# ElectronPhotonTestHarness.net
KiCad netlist of a schematic drawn in EAGLE
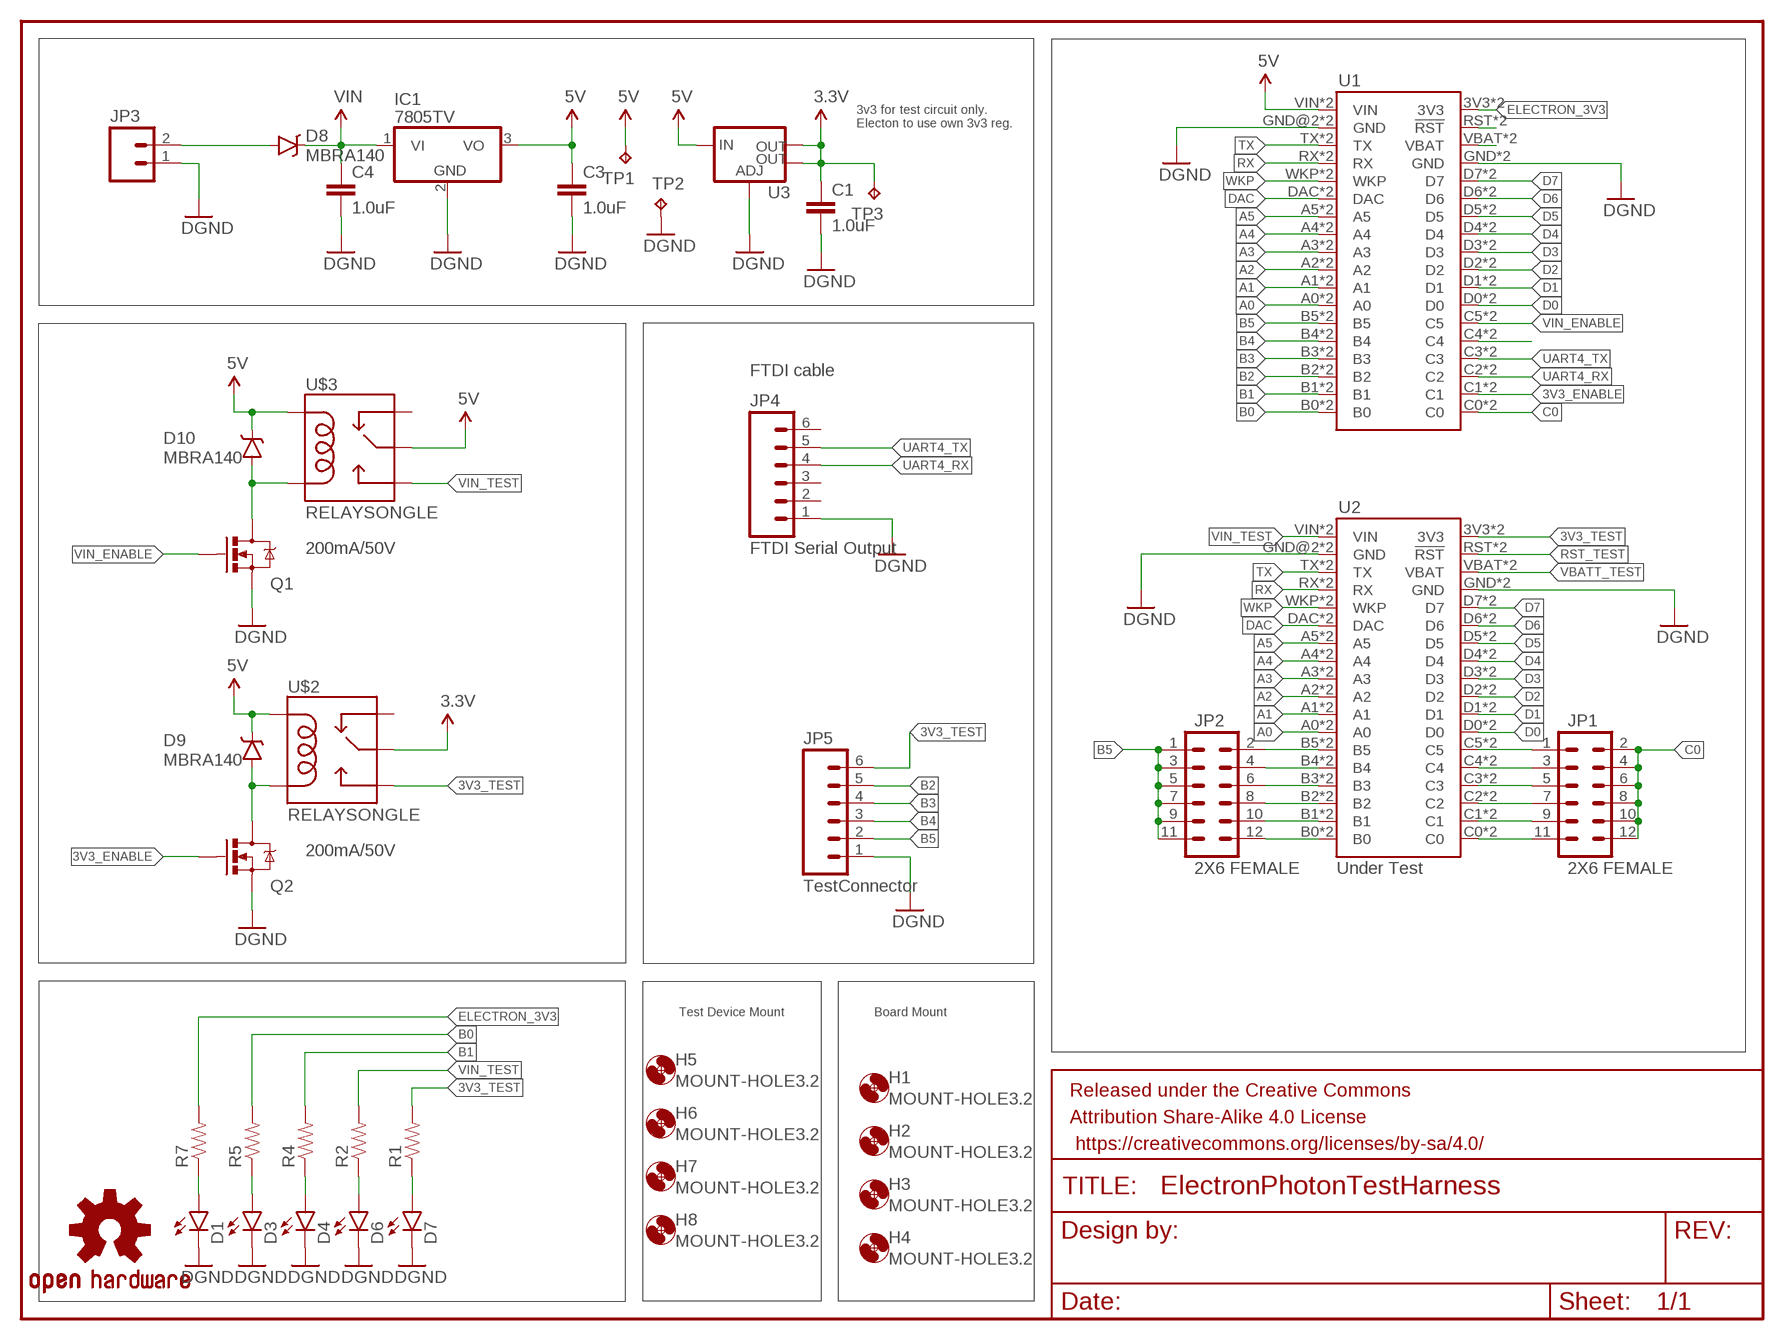
[diagram p0: schematic, sheet 1]

(export (version "E")
  (design (tool "Eeschema 10.0.6"))
  (components
    (comp (ref "C1")
      (value "1.0uF")
      (footprint "eagle-import:0805-CAP")
      (libsource (lib "eagle-import") (part "1.0UF-25V-+80/-20(0805){dblquote}"))
    )
    (comp (ref "C3")
      (value "1.0uF")
      (footprint "eagle-import:0805-CAP")
      (libsource (lib "eagle-import") (part "1.0UF-25V-+80/-20(0805){dblquote}"))
    )
    (comp (ref "C4")
      (value "1.0uF")
      (footprint "eagle-import:0805-CAP")
      (libsource (lib "eagle-import") (part "1.0UF-25V-+80/-20(0805){dblquote}"))
    )
    (comp (ref "D1")
      (value "LED1206-BOTTOM")
      (footprint "eagle-import:LED-1206-BOTTOM")
      (libsource (lib "eagle-import") (part "LED1206-BOTTOM"))
    )
    (comp (ref "D3")
      (value "LED1206")
      (footprint "eagle-import:LED-1206")
      (libsource (lib "eagle-import") (part "LED1206"))
    )
    (comp (ref "D4")
      (value "LED1206")
      (footprint "eagle-import:LED-1206")
      (libsource (lib "eagle-import") (part "LED1206"))
    )
    (comp (ref "D6")
      (value "LED1206")
      (footprint "eagle-import:LED-1206")
      (libsource (lib "eagle-import") (part "LED1206"))
    )
    (comp (ref "D7")
      (value "LED1206")
      (footprint "eagle-import:LED-1206")
      (libsource (lib "eagle-import") (part "LED1206"))
    )
    (comp (ref "D8")
      (value "MBRA140")
      (footprint "eagle-import:SMA-DIODE")
      (libsource (lib "eagle-import") (part "MBRA140"))
    )
    (comp (ref "D9")
      (value "MBRA140")
      (footprint "eagle-import:SMA-DIODE")
      (libsource (lib "eagle-import") (part "MBRA140"))
    )
    (comp (ref "D10")
      (value "MBRA140")
      (footprint "eagle-import:SMA-DIODE")
      (libsource (lib "eagle-import") (part "MBRA140"))
    )
    (comp (ref "FRAME1")
      (value "FRAME-LETTER")
      (footprint "eagle-import:CREATIVE_COMMONS")
      (libsource (lib "eagle-import") (part "FRAME-LETTER"))
    )
    (comp (ref "H1")
      (value "MOUNT-HOLE3.2")
      (footprint "eagle-import:3,2")
      (libsource (lib "eagle-import") (part "MOUNT-HOLE3.2"))
    )
    (comp (ref "H2")
      (value "MOUNT-HOLE3.2")
      (footprint "eagle-import:3,2")
      (libsource (lib "eagle-import") (part "MOUNT-HOLE3.2"))
    )
    (comp (ref "H3")
      (value "MOUNT-HOLE3.2")
      (footprint "eagle-import:3,2")
      (libsource (lib "eagle-import") (part "MOUNT-HOLE3.2"))
    )
    (comp (ref "H4")
      (value "MOUNT-HOLE3.2")
      (footprint "eagle-import:3,2")
      (libsource (lib "eagle-import") (part "MOUNT-HOLE3.2"))
    )
    (comp (ref "H5")
      (value "MOUNT-HOLE3.2")
      (footprint "eagle-import:3,2")
      (libsource (lib "eagle-import") (part "MOUNT-HOLE3.2"))
    )
    (comp (ref "H6")
      (value "MOUNT-HOLE3.2")
      (footprint "eagle-import:3,2")
      (libsource (lib "eagle-import") (part "MOUNT-HOLE3.2"))
    )
    (comp (ref "H7")
      (value "MOUNT-HOLE3.2")
      (footprint "eagle-import:3,2")
      (libsource (lib "eagle-import") (part "MOUNT-HOLE3.2"))
    )
    (comp (ref "H8")
      (value "MOUNT-HOLE3.2")
      (footprint "eagle-import:3,2")
      (libsource (lib "eagle-import") (part "MOUNT-HOLE3.2"))
    )
    (comp (ref "IC1")
      (value "7805TV")
      (footprint "eagle-import:TO220V")
      (libsource (lib "eagle-import") (part "78TV05"))
    )
    (comp (ref "JP1")
      (value "2X6 FEMALE")
      (footprint "eagle-import:2X6")
      (libsource (lib "eagle-import") (part "M06X2PTH_FEMALE"))
    )
    (comp (ref "JP2")
      (value "2X6 FEMALE")
      (footprint "eagle-import:2X6")
      (libsource (lib "eagle-import") (part "M06X2PTH_FEMALE"))
    )
    (comp (ref "JP3")
      (value "M025MM")
      (footprint "eagle-import:SCREWTERMINAL-5MM-2")
      (libsource (lib "eagle-import") (part "M025MM"))
    )
    (comp (ref "JP4")
      (value "FTDI Serial Output")
      (footprint "eagle-import:1X06")
      (libsource (lib "eagle-import") (part "M06SILK_FEMALE_PTH"))
    )
    (comp (ref "JP5")
      (value "TestConnector")
      (footprint "eagle-import:1X06")
      (libsource (lib "eagle-import") (part "M06SILK_FEMALE_PTH"))
    )
    (comp (ref "LOGO1")
      (value "OSHW-LOGOL")
      (footprint "eagle-import:OSHW-LOGO-L")
      (libsource (lib "eagle-import") (part "OSHW-LOGOL"))
    )
    (comp (ref "Q1")
      (value "200mA/50V")
      (footprint "eagle-import:SOT23-3")
      (libsource (lib "eagle-import") (part "MOSFET-NCHANNELBSS138"))
    )
    (comp (ref "Q2")
      (value "200mA/50V")
      (footprint "eagle-import:SOT23-3")
      (libsource (lib "eagle-import") (part "MOSFET-NCHANNELBSS138"))
    )
    (comp (ref "R1")
      (value "RESISTOR1206")
      (footprint "eagle-import:1206")
      (libsource (lib "eagle-import") (part "RESISTOR1206"))
    )
    (comp (ref "R2")
      (value "RESISTOR1206")
      (footprint "eagle-import:1206")
      (libsource (lib "eagle-import") (part "RESISTOR1206"))
    )
    (comp (ref "R4")
      (value "RESISTOR1206")
      (footprint "eagle-import:1206")
      (libsource (lib "eagle-import") (part "RESISTOR1206"))
    )
    (comp (ref "R5")
      (value "RESISTOR1206")
      (footprint "eagle-import:1206")
      (libsource (lib "eagle-import") (part "RESISTOR1206"))
    )
    (comp (ref "R7")
      (value "RESISTOR1206")
      (footprint "eagle-import:1206")
      (libsource (lib "eagle-import") (part "RESISTOR1206"))
    )
    (comp (ref "TP1")
      (value "TPTP12SQ")
      (footprint "eagle-import:TP12SQ")
      (libsource (lib "eagle-import") (part "TPTP12SQ"))
    )
    (comp (ref "TP2")
      (value "TPTP12SQ")
      (footprint "eagle-import:TP12SQ")
      (libsource (lib "eagle-import") (part "TPTP12SQ"))
    )
    (comp (ref "TP3")
      (value "TPTP12SQ")
      (footprint "eagle-import:TP12SQ")
      (libsource (lib "eagle-import") (part "TPTP12SQ"))
    )
    (comp (ref "U$2")
      (value "RELAYSONGLE")
      (footprint "eagle-import:SRD-5VDC-SL-C")
      (libsource (lib "eagle-import") (part "RELAYSONGLE"))
    )
    (comp (ref "U$3")
      (value "RELAYSONGLE")
      (footprint "eagle-import:SRD-5VDC-SL-C")
      (libsource (lib "eagle-import") (part "RELAYSONGLE"))
    )
    (comp (ref "U1")
      (value "ELECTRONDUALNAMED")
      (footprint "eagle-import:ELECTRON_SIMPLE_SILK_NAMES_DUAL")
      (libsource (lib "eagle-import") (part "ELECTRONDUALNAMED"))
    )
    (comp (ref "U2")
      (value "UnderTest")
      (footprint "eagle-import:ELECTRON_SIMPLE_SILK_NAMES_DUAL")
      (libsource (lib "eagle-import") (part "ELECTRONDUALNAMED"))
    )
    (comp (ref "U3")
      (value "V_REG_LM1117SOT223")
      (footprint "eagle-import:SOT223")
      (libsource (lib "eagle-import") (part "V_REG_LM1117SOT223"))
    )
  )
  (nets
    (net (code "1") (name "3.3V") (class "Default")
      (node (ref "C1") (pin "1") (pinfunction "1_1") (pintype "passive"))
      (node (ref "TP3") (pin "TP") (pinfunction "TP_TP") (pintype "input"))
      (node (ref "U$2") (pin "COMMON") (pinfunction "MAIN_COMMON") (pintype "bidirectional"))
      (node (ref "U3") (pin "2") (pinfunction "OUT_2") (pintype "output"))
      (node (ref "U3") (pin "4") (pinfunction "OUT_4") (pintype "output"))
    )
    (net (code "2") (name "3V3_ENABLE") (class "Default")
      (node (ref "Q2") (pin "1") (pinfunction "G_1") (pintype "passive"))
      (node (ref "U1") (pin "C1") (pinfunction "C1_C1") (pintype "bidirectional"))
      (node (ref "U1") (pin "C1_1") (pinfunction "C1_C1_1") (pintype "bidirectional"))
    )
    (net (code "3") (name "3V3_TEST") (class "Default")
      (node (ref "JP5") (pin "6") (pinfunction "6_6") (pintype "passive"))
      (node (ref "R1") (pin "2") (pinfunction "2_2") (pintype "passive"))
      (node (ref "U$2") (pin "OPEN") (pinfunction "NO_OPEN") (pintype "bidirectional"))
      (node (ref "U2") (pin "3V3") (pinfunction "3V3_3V3") (pintype "power_in"))
      (node (ref "U2") (pin "3V3_1") (pinfunction "3V3_3V3_1") (pintype "power_in"))
    )
    (net (code "4") (name "5V") (class "Default")
      (node (ref "C3") (pin "1") (pinfunction "1_1") (pintype "passive"))
      (node (ref "D10") (pin "C") (pinfunction "C_C") (pintype "passive"))
      (node (ref "D9") (pin "C") (pinfunction "C_C") (pintype "passive"))
      (node (ref "IC1") (pin "3") (pinfunction "VO_3") (pintype "passive"))
      (node (ref "TP1") (pin "TP") (pinfunction "TP_TP") (pintype "input"))
      (node (ref "U$2") (pin "COIL1") (pinfunction "COIL1_COIL1") (pintype "bidirectional"))
      (node (ref "U$3") (pin "COIL1") (pinfunction "COIL1_COIL1") (pintype "bidirectional"))
      (node (ref "U$3") (pin "COMMON") (pinfunction "MAIN_COMMON") (pintype "bidirectional"))
      (node (ref "U1") (pin "VIN") (pinfunction "VIN_VIN") (pintype "power_in"))
      (node (ref "U1") (pin "VIN_1B") (pinfunction "VIN_VIN_1B") (pintype "power_in"))
      (node (ref "U3") (pin "3") (pinfunction "IN_3") (pintype "input"))
    )
    (net (code "5") (name "A0") (class "Default")
      (node (ref "U1") (pin "A0") (pinfunction "A0_A0") (pintype "bidirectional"))
      (node (ref "U1") (pin "A0_1") (pinfunction "A0_A0_1") (pintype "bidirectional"))
      (node (ref "U2") (pin "A0") (pinfunction "A0_A0") (pintype "bidirectional"))
      (node (ref "U2") (pin "A0_1") (pinfunction "A0_A0_1") (pintype "bidirectional"))
    )
    (net (code "6") (name "A1") (class "Default")
      (node (ref "U1") (pin "A1") (pinfunction "A1_A1") (pintype "bidirectional"))
      (node (ref "U1") (pin "A1_1") (pinfunction "A1_A1_1") (pintype "bidirectional"))
      (node (ref "U2") (pin "A1") (pinfunction "A1_A1") (pintype "bidirectional"))
      (node (ref "U2") (pin "A1_1") (pinfunction "A1_A1_1") (pintype "bidirectional"))
    )
    (net (code "7") (name "A2") (class "Default")
      (node (ref "U1") (pin "A2") (pinfunction "A2_A2") (pintype "bidirectional"))
      (node (ref "U1") (pin "A2_1") (pinfunction "A2_A2_1") (pintype "bidirectional"))
      (node (ref "U2") (pin "A2") (pinfunction "A2_A2") (pintype "bidirectional"))
      (node (ref "U2") (pin "A2_1") (pinfunction "A2_A2_1") (pintype "bidirectional"))
    )
    (net (code "8") (name "A3") (class "Default")
      (node (ref "U1") (pin "A3") (pinfunction "A3_A3") (pintype "bidirectional"))
      (node (ref "U1") (pin "A3_1") (pinfunction "A3_A3_1") (pintype "bidirectional"))
      (node (ref "U2") (pin "A3") (pinfunction "A3_A3") (pintype "bidirectional"))
      (node (ref "U2") (pin "A3_1") (pinfunction "A3_A3_1") (pintype "bidirectional"))
    )
    (net (code "9") (name "A4") (class "Default")
      (node (ref "U1") (pin "A4") (pinfunction "A4_A4") (pintype "bidirectional"))
      (node (ref "U1") (pin "A4_1") (pinfunction "A4_A4_1") (pintype "bidirectional"))
      (node (ref "U2") (pin "A4") (pinfunction "A4_A4") (pintype "bidirectional"))
      (node (ref "U2") (pin "A4_1") (pinfunction "A4_A4_1") (pintype "bidirectional"))
    )
    (net (code "10") (name "A5") (class "Default")
      (node (ref "U1") (pin "A5") (pinfunction "A5_A5") (pintype "bidirectional"))
      (node (ref "U1") (pin "A5_1") (pinfunction "A5_A5_1") (pintype "bidirectional"))
      (node (ref "U2") (pin "A5") (pinfunction "A5_A5") (pintype "bidirectional"))
      (node (ref "U2") (pin "A5_1") (pinfunction "A5_A5_1") (pintype "bidirectional"))
    )
    (net (code "11") (name "B0") (class "Default")
      (node (ref "R5") (pin "2") (pinfunction "2_2") (pintype "passive"))
      (node (ref "U1") (pin "B0") (pinfunction "B0_B0") (pintype "bidirectional"))
      (node (ref "U1") (pin "B0_1") (pinfunction "B0_B0_1") (pintype "bidirectional"))
    )
    (net (code "12") (name "B1") (class "Default")
      (node (ref "R4") (pin "2") (pinfunction "2_2") (pintype "passive"))
      (node (ref "U1") (pin "B1") (pinfunction "B1_B1") (pintype "bidirectional"))
      (node (ref "U1") (pin "B1_1") (pinfunction "B1_B1_1") (pintype "bidirectional"))
    )
    (net (code "13") (name "B2") (class "Default")
      (node (ref "JP5") (pin "5") (pinfunction "5_5") (pintype "passive"))
      (node (ref "U1") (pin "B2") (pinfunction "B2_B2") (pintype "bidirectional"))
      (node (ref "U1") (pin "B2_1") (pinfunction "B2_B2_1") (pintype "bidirectional"))
    )
    (net (code "14") (name "B3") (class "Default")
      (node (ref "JP5") (pin "4") (pinfunction "4_4") (pintype "passive"))
      (node (ref "U1") (pin "B3") (pinfunction "B3_B3") (pintype "bidirectional"))
      (node (ref "U1") (pin "B3_1") (pinfunction "B3_B3_1") (pintype "bidirectional"))
    )
    (net (code "15") (name "B4") (class "Default")
      (node (ref "JP5") (pin "3") (pinfunction "3_3") (pintype "passive"))
      (node (ref "U1") (pin "B4") (pinfunction "B4_B4") (pintype "bidirectional"))
      (node (ref "U1") (pin "B4_1") (pinfunction "B4_B4_1") (pintype "bidirectional"))
    )
    (net (code "16") (name "B5") (class "Default")
      (node (ref "JP2") (pin "1") (pinfunction "1_1") (pintype "passive"))
      (node (ref "JP2") (pin "11") (pinfunction "11_11") (pintype "passive"))
      (node (ref "JP2") (pin "3") (pinfunction "3_3") (pintype "passive"))
      (node (ref "JP2") (pin "5") (pinfunction "5_5") (pintype "passive"))
      (node (ref "JP2") (pin "7") (pinfunction "7_7") (pintype "passive"))
      (node (ref "JP2") (pin "9") (pinfunction "9_9") (pintype "passive"))
      (node (ref "JP5") (pin "2") (pinfunction "2_2") (pintype "passive"))
      (node (ref "U1") (pin "B5") (pinfunction "B5_B5") (pintype "bidirectional"))
      (node (ref "U1") (pin "B5_1") (pinfunction "B5_B5_1") (pintype "bidirectional"))
    )
    (net (code "17") (name "C0") (class "Default")
      (node (ref "JP1") (pin "10") (pinfunction "10_10") (pintype "passive"))
      (node (ref "JP1") (pin "12") (pinfunction "12_12") (pintype "passive"))
      (node (ref "JP1") (pin "2") (pinfunction "2_2") (pintype "passive"))
      (node (ref "JP1") (pin "4") (pinfunction "4_4") (pintype "passive"))
      (node (ref "JP1") (pin "6") (pinfunction "6_6") (pintype "passive"))
      (node (ref "JP1") (pin "8") (pinfunction "8_8") (pintype "passive"))
      (node (ref "U1") (pin "C0") (pinfunction "C0_C0") (pintype "bidirectional"))
      (node (ref "U1") (pin "C0_1") (pinfunction "C0_C0_1") (pintype "bidirectional"))
    )
    (net (code "18") (name "D0") (class "Default")
      (node (ref "U1") (pin "D0") (pinfunction "D0_D0") (pintype "bidirectional"))
      (node (ref "U1") (pin "D0_1") (pinfunction "D0_D0_1") (pintype "bidirectional"))
      (node (ref "U2") (pin "D0") (pinfunction "D0_D0") (pintype "bidirectional"))
      (node (ref "U2") (pin "D0_1") (pinfunction "D0_D0_1") (pintype "bidirectional"))
    )
    (net (code "19") (name "D1") (class "Default")
      (node (ref "U1") (pin "D1") (pinfunction "D1_D1") (pintype "bidirectional"))
      (node (ref "U1") (pin "D1_1") (pinfunction "D1_D1_1") (pintype "bidirectional"))
      (node (ref "U2") (pin "D1") (pinfunction "D1_D1") (pintype "bidirectional"))
      (node (ref "U2") (pin "D1_1") (pinfunction "D1_D1_1") (pintype "bidirectional"))
    )
    (net (code "20") (name "D2") (class "Default")
      (node (ref "U1") (pin "D2") (pinfunction "D2_D2") (pintype "bidirectional"))
      (node (ref "U1") (pin "D2_1") (pinfunction "D2_D2_1") (pintype "bidirectional"))
      (node (ref "U2") (pin "D2") (pinfunction "D2_D2") (pintype "bidirectional"))
      (node (ref "U2") (pin "D2_1") (pinfunction "D2_D2_1") (pintype "bidirectional"))
    )
    (net (code "21") (name "D3") (class "Default")
      (node (ref "U1") (pin "D3") (pinfunction "D3_D3") (pintype "bidirectional"))
      (node (ref "U1") (pin "D3_1") (pinfunction "D3_D3_1") (pintype "bidirectional"))
      (node (ref "U2") (pin "D3") (pinfunction "D3_D3") (pintype "bidirectional"))
      (node (ref "U2") (pin "D3_1") (pinfunction "D3_D3_1") (pintype "bidirectional"))
    )
    (net (code "22") (name "D4") (class "Default")
      (node (ref "U1") (pin "D4") (pinfunction "D4_D4") (pintype "bidirectional"))
      (node (ref "U1") (pin "D4_1") (pinfunction "D4_D4_1") (pintype "bidirectional"))
      (node (ref "U2") (pin "D4") (pinfunction "D4_D4") (pintype "bidirectional"))
      (node (ref "U2") (pin "D4_1") (pinfunction "D4_D4_1") (pintype "bidirectional"))
    )
    (net (code "23") (name "D5") (class "Default")
      (node (ref "U1") (pin "D5") (pinfunction "D5_D5") (pintype "bidirectional"))
      (node (ref "U1") (pin "D5_1") (pinfunction "D5_D5_1") (pintype "bidirectional"))
      (node (ref "U2") (pin "D5") (pinfunction "D5_D5") (pintype "bidirectional"))
      (node (ref "U2") (pin "D5_1") (pinfunction "D5_D5_1") (pintype "bidirectional"))
    )
    (net (code "24") (name "D6") (class "Default")
      (node (ref "U1") (pin "D6") (pinfunction "D6_D6") (pintype "bidirectional"))
      (node (ref "U1") (pin "D6_1") (pinfunction "D6_D6_1") (pintype "bidirectional"))
      (node (ref "U2") (pin "D6") (pinfunction "D6_D6") (pintype "bidirectional"))
      (node (ref "U2") (pin "D6_1") (pinfunction "D6_D6_1") (pintype "bidirectional"))
    )
    (net (code "25") (name "D7") (class "Default")
      (node (ref "U1") (pin "D7") (pinfunction "D7_D7") (pintype "bidirectional"))
      (node (ref "U1") (pin "D7_1") (pinfunction "D7_D7_1") (pintype "bidirectional"))
      (node (ref "U2") (pin "D7") (pinfunction "D7_D7") (pintype "bidirectional"))
      (node (ref "U2") (pin "D7_1") (pinfunction "D7_D7_1") (pintype "bidirectional"))
    )
    (net (code "26") (name "DAC") (class "Default")
      (node (ref "U1") (pin "DAC") (pinfunction "DAC_DAC") (pintype "bidirectional"))
      (node (ref "U1") (pin "DAC_1") (pinfunction "DAC_DAC_1") (pintype "bidirectional"))
      (node (ref "U2") (pin "DAC") (pinfunction "DAC_DAC") (pintype "bidirectional"))
      (node (ref "U2") (pin "DAC_1") (pinfunction "DAC_DAC_1") (pintype "bidirectional"))
    )
    (net (code "27") (name "DGND") (class "Default")
      (node (ref "C1") (pin "2") (pinfunction "2_2") (pintype "passive"))
      (node (ref "C3") (pin "2") (pinfunction "2_2") (pintype "passive"))
      (node (ref "C4") (pin "2") (pinfunction "2_2") (pintype "passive"))
      (node (ref "D1") (pin "C") (pinfunction "C_C") (pintype "passive"))
      (node (ref "D3") (pin "C") (pinfunction "C_C") (pintype "passive"))
      (node (ref "D4") (pin "C") (pinfunction "C_C") (pintype "passive"))
      (node (ref "D6") (pin "C") (pinfunction "C_C") (pintype "passive"))
      (node (ref "D7") (pin "C") (pinfunction "C_C") (pintype "passive"))
      (node (ref "IC1") (pin "2") (pinfunction "GND_2") (pintype "passive"))
      (node (ref "JP3") (pin "1") (pinfunction "1_1") (pintype "passive"))
      (node (ref "JP4") (pin "1") (pinfunction "1_1") (pintype "passive"))
      (node (ref "JP5") (pin "1") (pinfunction "1_1") (pintype "passive"))
      (node (ref "Q1") (pin "2") (pinfunction "S_2") (pintype "passive"))
      (node (ref "Q2") (pin "2") (pinfunction "S_2") (pintype "passive"))
      (node (ref "TP2") (pin "TP") (pinfunction "TP_TP") (pintype "input"))
      (node (ref "U1") (pin "GND") (pinfunction "GND_GND") (pintype "power_in"))
      (node (ref "U1") (pin "GND@2") (pinfunction "GND_GND@2") (pintype "power_in"))
      (node (ref "U1") (pin "GND_1") (pinfunction "GND_GND_1") (pintype "power_in"))
      (node (ref "U1") (pin "GND_1B") (pinfunction "GND_GND_1B") (pintype "power_in"))
      (node (ref "U2") (pin "GND") (pinfunction "GND_GND") (pintype "power_in"))
      (node (ref "U2") (pin "GND@2") (pinfunction "GND_GND@2") (pintype "power_in"))
      (node (ref "U2") (pin "GND_1") (pinfunction "GND_GND_1") (pintype "power_in"))
      (node (ref "U2") (pin "GND_1B") (pinfunction "GND_GND_1B") (pintype "power_in"))
      (node (ref "U3") (pin "1") (pinfunction "ADJ_1") (pintype "input"))
    )
    (net (code "28") (name "ELECTRON_3V3") (class "Default")
      (node (ref "R7") (pin "2") (pinfunction "2_2") (pintype "passive"))
      (node (ref "U1") (pin "3V3") (pinfunction "3V3_3V3") (pintype "power_in"))
      (node (ref "U1") (pin "3V3_1") (pinfunction "3V3_3V3_1") (pintype "power_in"))
    )
    (net (code "29") (name "Net-(D1-PadA)") (class "Default")
      (node (ref "D1") (pin "A") (pinfunction "A_A") (pintype "passive"))
      (node (ref "R7") (pin "1") (pinfunction "1_1") (pintype "passive"))
    )
    (net (code "30") (name "Net-(D3-PadA)") (class "Default")
      (node (ref "D3") (pin "A") (pinfunction "A_A") (pintype "passive"))
      (node (ref "R5") (pin "1") (pinfunction "1_1") (pintype "passive"))
    )
    (net (code "31") (name "Net-(D4-PadA)") (class "Default")
      (node (ref "D4") (pin "A") (pinfunction "A_A") (pintype "passive"))
      (node (ref "R4") (pin "1") (pinfunction "1_1") (pintype "passive"))
    )
    (net (code "32") (name "Net-(D6-PadA)") (class "Default")
      (node (ref "D6") (pin "A") (pinfunction "A_A") (pintype "passive"))
      (node (ref "R2") (pin "1") (pinfunction "1_1") (pintype "passive"))
    )
    (net (code "33") (name "Net-(D7-PadA)") (class "Default")
      (node (ref "D7") (pin "A") (pinfunction "A_A") (pintype "passive"))
      (node (ref "R1") (pin "1") (pinfunction "1_1") (pintype "passive"))
    )
    (net (code "34") (name "Net-(D8-PadA)") (class "Default")
      (node (ref "D8") (pin "A") (pinfunction "A_A") (pintype "passive"))
      (node (ref "JP3") (pin "2") (pinfunction "2_2") (pintype "passive"))
    )
    (net (code "35") (name "Net-(JP1-Pad1)") (class "Default")
      (node (ref "JP1") (pin "1") (pinfunction "1_1") (pintype "passive"))
      (node (ref "U2") (pin "C5") (pinfunction "C5_C5") (pintype "bidirectional"))
      (node (ref "U2") (pin "C5_1") (pinfunction "C5_C5_1") (pintype "bidirectional"))
    )
    (net (code "36") (name "Net-(JP1-Pad3)") (class "Default")
      (node (ref "JP1") (pin "3") (pinfunction "3_3") (pintype "passive"))
      (node (ref "U2") (pin "C4") (pinfunction "C4_C4") (pintype "bidirectional"))
      (node (ref "U2") (pin "C4_1") (pinfunction "C4_C4_1") (pintype "bidirectional"))
    )
    (net (code "37") (name "Net-(JP1-Pad5)") (class "Default")
      (node (ref "JP1") (pin "5") (pinfunction "5_5") (pintype "passive"))
      (node (ref "U2") (pin "C3") (pinfunction "C3_C3") (pintype "bidirectional"))
      (node (ref "U2") (pin "C3_1") (pinfunction "C3_C3_1") (pintype "bidirectional"))
    )
    (net (code "38") (name "Net-(JP1-Pad7)") (class "Default")
      (node (ref "JP1") (pin "7") (pinfunction "7_7") (pintype "passive"))
      (node (ref "U2") (pin "C2") (pinfunction "C2_C2") (pintype "bidirectional"))
      (node (ref "U2") (pin "C2_1") (pinfunction "C2_C2_1") (pintype "bidirectional"))
    )
    (net (code "39") (name "Net-(JP1-Pad9)") (class "Default")
      (node (ref "JP1") (pin "9") (pinfunction "9_9") (pintype "passive"))
      (node (ref "U2") (pin "C1") (pinfunction "C1_C1") (pintype "bidirectional"))
      (node (ref "U2") (pin "C1_1") (pinfunction "C1_C1_1") (pintype "bidirectional"))
    )
    (net (code "40") (name "Net-(JP1-Pad11)") (class "Default")
      (node (ref "JP1") (pin "11") (pinfunction "11_11") (pintype "passive"))
      (node (ref "U2") (pin "C0") (pinfunction "C0_C0") (pintype "bidirectional"))
      (node (ref "U2") (pin "C0_1") (pinfunction "C0_C0_1") (pintype "bidirectional"))
    )
    (net (code "41") (name "Net-(JP2-Pad2)") (class "Default")
      (node (ref "JP2") (pin "2") (pinfunction "2_2") (pintype "passive"))
      (node (ref "U2") (pin "B5") (pinfunction "B5_B5") (pintype "bidirectional"))
      (node (ref "U2") (pin "B5_1") (pinfunction "B5_B5_1") (pintype "bidirectional"))
    )
    (net (code "42") (name "Net-(JP2-Pad4)") (class "Default")
      (node (ref "JP2") (pin "4") (pinfunction "4_4") (pintype "passive"))
      (node (ref "U2") (pin "B4") (pinfunction "B4_B4") (pintype "bidirectional"))
      (node (ref "U2") (pin "B4_1") (pinfunction "B4_B4_1") (pintype "bidirectional"))
    )
    (net (code "43") (name "Net-(JP2-Pad6)") (class "Default")
      (node (ref "JP2") (pin "6") (pinfunction "6_6") (pintype "passive"))
      (node (ref "U2") (pin "B3") (pinfunction "B3_B3") (pintype "bidirectional"))
      (node (ref "U2") (pin "B3_1") (pinfunction "B3_B3_1") (pintype "bidirectional"))
    )
    (net (code "44") (name "Net-(JP2-Pad8)") (class "Default")
      (node (ref "JP2") (pin "8") (pinfunction "8_8") (pintype "passive"))
      (node (ref "U2") (pin "B2") (pinfunction "B2_B2") (pintype "bidirectional"))
      (node (ref "U2") (pin "B2_1") (pinfunction "B2_B2_1") (pintype "bidirectional"))
    )
    (net (code "45") (name "Net-(JP2-Pad10)") (class "Default")
      (node (ref "JP2") (pin "10") (pinfunction "10_10") (pintype "passive"))
      (node (ref "U2") (pin "B1") (pinfunction "B1_B1") (pintype "bidirectional"))
      (node (ref "U2") (pin "B1_1") (pinfunction "B1_B1_1") (pintype "bidirectional"))
    )
    (net (code "46") (name "Net-(JP2-Pad12)") (class "Default")
      (node (ref "JP2") (pin "12") (pinfunction "12_12") (pintype "passive"))
      (node (ref "U2") (pin "B0") (pinfunction "B0_B0") (pintype "bidirectional"))
      (node (ref "U2") (pin "B0_1") (pinfunction "B0_B0_1") (pintype "bidirectional"))
    )
    (net (code "47") (name "Net-(Q1-D)") (class "Default")
      (node (ref "D10") (pin "A") (pinfunction "A_A") (pintype "passive"))
      (node (ref "Q1") (pin "3") (pinfunction "D_3") (pintype "passive"))
      (node (ref "U$3") (pin "COIL2") (pinfunction "COIL2_COIL2") (pintype "bidirectional"))
    )
    (net (code "48") (name "Net-(Q2-D)") (class "Default")
      (node (ref "D9") (pin "A") (pinfunction "A_A") (pintype "passive"))
      (node (ref "Q2") (pin "3") (pinfunction "D_3") (pintype "passive"))
      (node (ref "U$2") (pin "COIL2") (pinfunction "COIL2_COIL2") (pintype "bidirectional"))
    )
    (net (code "49") (name "Net-(U1-C4-PadC4_1)") (class "Default")
      (node (ref "U1") (pin "C4") (pinfunction "C4_C4") (pintype "bidirectional"))
      (node (ref "U1") (pin "C4_1") (pinfunction "C4_C4_1") (pintype "bidirectional"))
    )
    (net (code "50") (name "Net-(U1-PadVBAT)") (class "Default")
      (node (ref "U1") (pin "VBAT") (pinfunction "VBAT_VBAT") (pintype "passive"))
      (node (ref "U1") (pin "VBATT_1") (pinfunction "VBAT_VBATT_1") (pintype "passive"))
    )
    (net (code "51") (name "Net-(U1-~{RST}-PadRST)") (class "Default")
      (node (ref "U1") (pin "RST") (pinfunction "~{RST}_RST") (pintype "bidirectional"))
      (node (ref "U1") (pin "RST_1") (pinfunction "~{RST}_RST_1") (pintype "bidirectional"))
    )
    (net (code "52") (name "RST_TEST") (class "Default")
      (node (ref "U2") (pin "RST") (pinfunction "~{RST}_RST") (pintype "bidirectional"))
      (node (ref "U2") (pin "RST_1") (pinfunction "~{RST}_RST_1") (pintype "bidirectional"))
    )
    (net (code "53") (name "RX") (class "Default")
      (node (ref "U1") (pin "RX") (pinfunction "RX_RX") (pintype "bidirectional"))
      (node (ref "U1") (pin "RX_1") (pinfunction "RX_RX_1") (pintype "bidirectional"))
      (node (ref "U2") (pin "RX") (pinfunction "RX_RX") (pintype "bidirectional"))
      (node (ref "U2") (pin "RX_1") (pinfunction "RX_RX_1") (pintype "bidirectional"))
    )
    (net (code "54") (name "TX") (class "Default")
      (node (ref "U1") (pin "TX") (pinfunction "TX_TX") (pintype "bidirectional"))
      (node (ref "U1") (pin "TX_1") (pinfunction "TX_TX_1") (pintype "bidirectional"))
      (node (ref "U2") (pin "TX") (pinfunction "TX_TX") (pintype "bidirectional"))
      (node (ref "U2") (pin "TX_1") (pinfunction "TX_TX_1") (pintype "bidirectional"))
    )
    (net (code "55") (name "UART4_RX") (class "Default")
      (node (ref "JP4") (pin "4") (pinfunction "4_4") (pintype "passive"))
      (node (ref "U1") (pin "C2") (pinfunction "C2_C2") (pintype "bidirectional"))
      (node (ref "U1") (pin "C2_1") (pinfunction "C2_C2_1") (pintype "bidirectional"))
    )
    (net (code "56") (name "UART4_TX") (class "Default")
      (node (ref "JP4") (pin "5") (pinfunction "5_5") (pintype "passive"))
      (node (ref "U1") (pin "C3") (pinfunction "C3_C3") (pintype "bidirectional"))
      (node (ref "U1") (pin "C3_1") (pinfunction "C3_C3_1") (pintype "bidirectional"))
    )
    (net (code "57") (name "VBATT_TEST") (class "Default")
      (node (ref "U2") (pin "VBAT") (pinfunction "VBAT_VBAT") (pintype "passive"))
      (node (ref "U2") (pin "VBATT_1") (pinfunction "VBAT_VBATT_1") (pintype "passive"))
    )
    (net (code "58") (name "VIN") (class "Default")
      (node (ref "C4") (pin "1") (pinfunction "1_1") (pintype "passive"))
      (node (ref "D8") (pin "C") (pinfunction "C_C") (pintype "passive"))
      (node (ref "IC1") (pin "1") (pinfunction "VI_1") (pintype "input"))
    )
    (net (code "59") (name "VIN_ENABLE") (class "Default")
      (node (ref "Q1") (pin "1") (pinfunction "G_1") (pintype "passive"))
      (node (ref "U1") (pin "C5") (pinfunction "C5_C5") (pintype "bidirectional"))
      (node (ref "U1") (pin "C5_1") (pinfunction "C5_C5_1") (pintype "bidirectional"))
    )
    (net (code "60") (name "VIN_TEST") (class "Default")
      (node (ref "R2") (pin "2") (pinfunction "2_2") (pintype "passive"))
      (node (ref "U$3") (pin "OPEN") (pinfunction "NO_OPEN") (pintype "bidirectional"))
      (node (ref "U2") (pin "VIN") (pinfunction "VIN_VIN") (pintype "power_in"))
      (node (ref "U2") (pin "VIN_1B") (pinfunction "VIN_VIN_1B") (pintype "power_in"))
    )
    (net (code "61") (name "WKP") (class "Default")
      (node (ref "U1") (pin "WKP") (pinfunction "WKP_WKP") (pintype "bidirectional"))
      (node (ref "U1") (pin "WKP_1") (pinfunction "WKP_WKP_1") (pintype "bidirectional"))
      (node (ref "U2") (pin "WKP") (pinfunction "WKP_WKP") (pintype "bidirectional"))
      (node (ref "U2") (pin "WKP_1") (pinfunction "WKP_WKP_1") (pintype "bidirectional"))
    )
    (net (code "62") (name "unconnected-(JP4-Pad2)") (class "Default")
      (node (ref "JP4") (pin "2") (pinfunction "2_2") (pintype "passive"))
    )
    (net (code "63") (name "unconnected-(JP4-Pad3)") (class "Default")
      (node (ref "JP4") (pin "3") (pinfunction "3_3") (pintype "passive"))
    )
    (net (code "64") (name "unconnected-(JP4-Pad6)") (class "Default")
      (node (ref "JP4") (pin "6") (pinfunction "6_6") (pintype "passive"))
    )
    (net (code "65") (name "unconnected-(U$2-NC-PadCLOSED)") (class "Default")
      (node (ref "U$2") (pin "CLOSED") (pinfunction "NC_CLOSED") (pintype "bidirectional"))
    )
    (net (code "66") (name "unconnected-(U$3-NC-PadCLOSED)") (class "Default")
      (node (ref "U$3") (pin "CLOSED") (pinfunction "NC_CLOSED") (pintype "bidirectional"))
    )
  )
)
